# spi_adc.net
KiCad netlist of a schematic drawn in Altium Designer
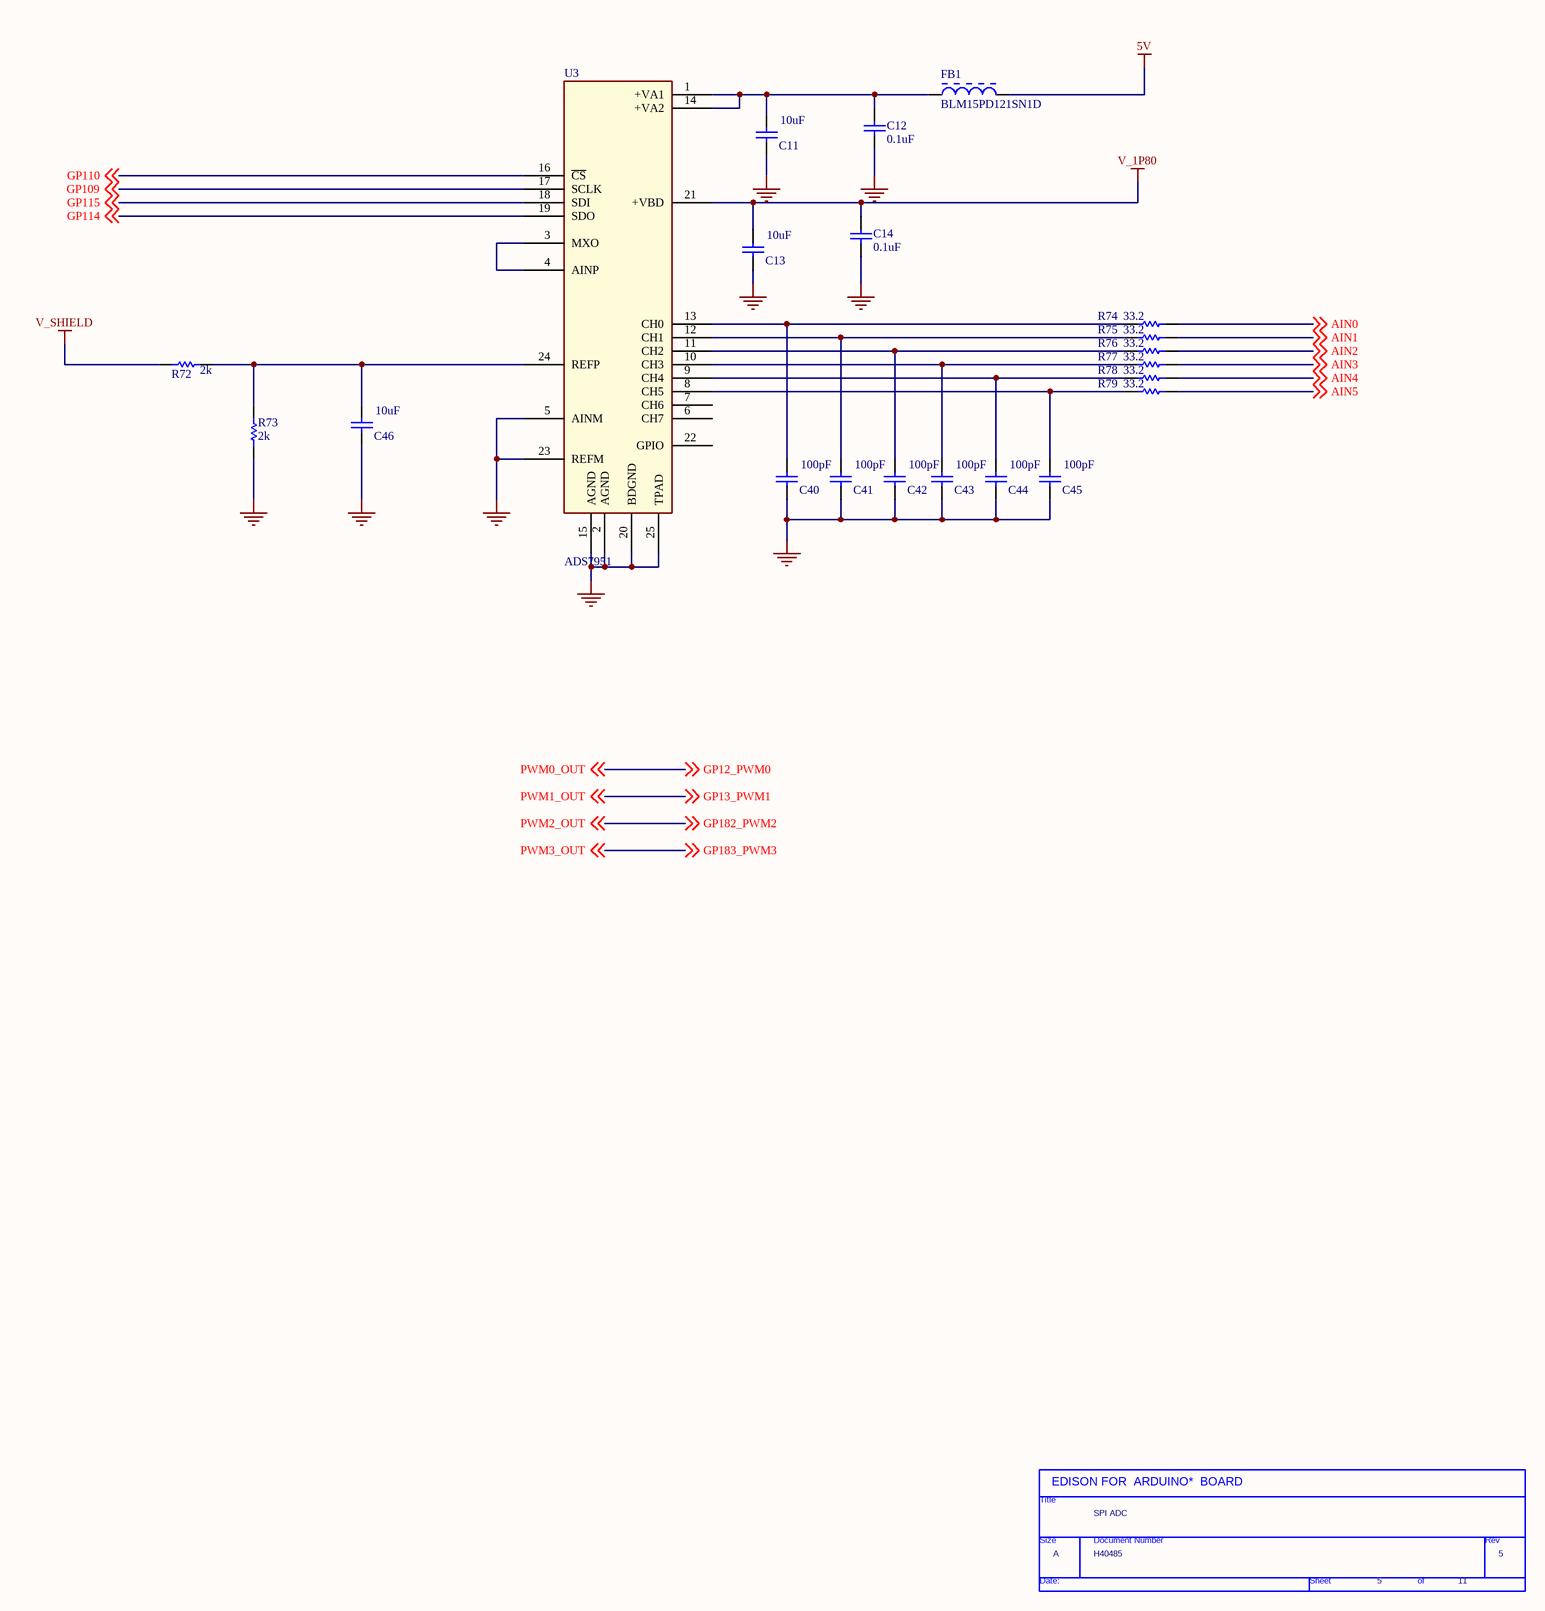
[diagram p0: spi_adc.SchDoc]

(export (version "E")
  (design (tool "Eeschema 10.0.6"))
  (components
    (comp (ref "*")
      (value "TitleBlock0")
      (fields
        (field (name "PAGE COUNT") "11")
        (field (name "PAGE NUMBER") "5")
        (field (name "PAGE SIZE") "A")
        (field (name "TITLE") "SPI ADC")
        (field (name "REVCODE") "5")
        (field (name "DOC") "H40485")
      )
      (libsource (lib "*") (part "TitleBlock0"))
    )
    (comp (ref "C11")
      (value "10uF")
      (footprint "CAPC0402(1005)60_L")
      (description "CAP 10uF 6.3V ±20% 0402 (1005 Metric) Thickness 0.6mm SMD")
      (fields (field (name "TOLERANCE") "±20%") (field (name "Comment") "CAP 10uF 6.3V 0402(1005)"))
      (libsource (lib "Altium Content Vault") (part "CMP-1034-02138-1"))
    )
    (comp (ref "C12")
      (value "0.1uF")
      (footprint "CAPC0201(0603)33_L")
      (description "CAP 1.5nF 10V ±20% 0201 (0603 Metric) Thickness 0.33mm SMD")
      (fields (field (name "TOLERANCE") "±20%") (field (name "Comment") "CAP 1.5nF 10V 0201(0603)"))
      (libsource (lib "Altium Content Vault") (part "CMP-1033-00601-1"))
    )
    (comp (ref "C13")
      (value "10uF")
      (footprint "CAPC0402(1005)60_L")
      (description "CAP 10uF 6.3V ±20% 0402 (1005 Metric) Thickness 0.6mm SMD")
      (fields (field (name "TOLERANCE") "±20%") (field (name "Comment") "CAP 10uF 6.3V 0402(1005)"))
      (libsource (lib "Altium Content Vault") (part "CMP-1034-02138-1"))
    )
    (comp (ref "C14")
      (value "0.1uF")
      (footprint "CAPC0201(0603)33_L")
      (description "CAP 1.5nF 10V ±20% 0201 (0603 Metric) Thickness 0.33mm SMD")
      (fields (field (name "TOLERANCE") "±20%") (field (name "Comment") "CAP 1.5nF 10V 0201(0603)"))
      (libsource (lib "Altium Content Vault") (part "CMP-1033-00601-1"))
    )
    (comp (ref "C40")
      (value "100pF")
      (footprint "CAPC0201(0603)33_M")
      (description "CAP 100pF 25V ±5% 0201 (0603 Metric) Thickness 0.33mm SMD")
      (fields (field (name "TOLERANCE") "±5%") (field (name "Comment") "CAP 100pF 25V 0201(0603)"))
      (libsource (lib "Altium Content Vault") (part "CMP-1033-00493-1"))
    )
    (comp (ref "C41")
      (value "100pF")
      (footprint "CAPC0201(0603)33_M")
      (description "CAP 100pF 25V ±5% 0201 (0603 Metric) Thickness 0.33mm SMD")
      (fields (field (name "TOLERANCE") "±5%") (field (name "Comment") "CAP 100pF 25V 0201(0603)"))
      (libsource (lib "Altium Content Vault") (part "CMP-1033-00493-1"))
    )
    (comp (ref "C42")
      (value "100pF")
      (footprint "CAPC0201(0603)33_M")
      (description "CAP 100pF 25V ±5% 0201 (0603 Metric) Thickness 0.33mm SMD")
      (fields (field (name "TOLERANCE") "±5%") (field (name "Comment") "CAP 100pF 25V 0201(0603)"))
      (libsource (lib "Altium Content Vault") (part "CMP-1033-00493-1"))
    )
    (comp (ref "C43")
      (value "100pF")
      (footprint "CAPC0201(0603)33_M")
      (description "CAP 100pF 25V ±5% 0201 (0603 Metric) Thickness 0.33mm SMD")
      (fields (field (name "TOLERANCE") "±5%") (field (name "Comment") "CAP 100pF 25V 0201(0603)"))
      (libsource (lib "Altium Content Vault") (part "CMP-1033-00493-1"))
    )
    (comp (ref "C44")
      (value "100pF")
      (footprint "CAPC0201(0603)33_M")
      (description "CAP 100pF 25V ±5% 0201 (0603 Metric) Thickness 0.33mm SMD")
      (fields (field (name "TOLERANCE") "±5%") (field (name "Comment") "CAP 100pF 25V 0201(0603)"))
      (libsource (lib "Altium Content Vault") (part "CMP-1033-00493-1"))
    )
    (comp (ref "C45")
      (value "100pF")
      (footprint "CAPC0201(0603)33_M")
      (description "CAP 100pF 25V ±5% 0201 (0603 Metric) Thickness 0.33mm SMD")
      (fields (field (name "TOLERANCE") "±5%") (field (name "Comment") "CAP 100pF 25V 0201(0603)"))
      (libsource (lib "Altium Content Vault") (part "CMP-1033-00493-1"))
    )
    (comp (ref "C46")
      (value "10uF")
      (footprint "CAPC0402(1005)60_L")
      (description "CAP 10uF 6.3V ±20% 0402 (1005 Metric) Thickness 0.6mm SMD")
      (fields (field (name "TOLERANCE") "±20%") (field (name "Comment") "CAP 10uF 6.3V 0402(1005)"))
      (libsource (lib "Altium Content Vault") (part "CMP-1034-02138-1"))
    )
    (comp (ref "FB1")
      (value "BLM15PD121SN1D")
      (footprint "MURA-BLM15-CHIP-2_V")
      (fields (field (name "MANUFACTURER") "Murata"))
      (libsource (lib "Altium Content Vault") (part "CMP-0686-00281-1"))
    )
    (comp (ref "R72")
      (value "2k")
      (footprint "RESC0201(0603)_N")
      (description "2K 0.05W 5% 0201 (0603 Metric)  SMD")
      (fields (field (name "TOLERANCE") "1 %") (field (name "POWER") "0.05 W"))
      (libsource (lib "Altium Content Vault") (part "CMP-1010-00081-1"))
    )
    (comp (ref "R73")
      (value "2k")
      (footprint "RESC0201(0603)_N")
      (description "2K 0.05W 5% 0201 (0603 Metric)  SMD")
      (fields (field (name "TOLERANCE") "1 %") (field (name "POWER") "0.05 W"))
      (libsource (lib "Altium Content Vault") (part "CMP-1010-00081-1"))
    )
    (comp (ref "R74")
      (value "33.2")
      (footprint "RESC0201(0603)_L")
      (description "33R2 0.05W 1% 0201 (0603 Metric)  SMD")
      (fields (field (name "POWER") "0.05 W") (field (name "TOLERANCE") "1 %"))
      (libsource (lib "Altium Content Vault") (part "CMP-1010-00248-1"))
    )
    (comp (ref "R75")
      (value "33.2")
      (footprint "RESC0201(0603)_L")
      (description "33R2 0.05W 1% 0201 (0603 Metric)  SMD")
      (fields (field (name "POWER") "0.05 W") (field (name "TOLERANCE") "1 %"))
      (libsource (lib "Altium Content Vault") (part "CMP-1010-00248-1"))
    )
    (comp (ref "R76")
      (value "33.2")
      (footprint "RESC0201(0603)_L")
      (description "33R2 0.05W 1% 0201 (0603 Metric)  SMD")
      (fields (field (name "POWER") "0.05 W") (field (name "TOLERANCE") "1 %"))
      (libsource (lib "Altium Content Vault") (part "CMP-1010-00248-1"))
    )
    (comp (ref "R77")
      (value "33.2")
      (footprint "RESC0201(0603)_L")
      (description "33R2 0.05W 1% 0201 (0603 Metric)  SMD")
      (fields (field (name "POWER") "0.05 W") (field (name "TOLERANCE") "1 %"))
      (libsource (lib "Altium Content Vault") (part "CMP-1010-00248-1"))
    )
    (comp (ref "R78")
      (value "33.2")
      (footprint "RESC0201(0603)_L")
      (description "33R2 0.05W 1% 0201 (0603 Metric)  SMD")
      (fields (field (name "POWER") "0.05 W") (field (name "TOLERANCE") "1 %"))
      (libsource (lib "Altium Content Vault") (part "CMP-1010-00248-1"))
    )
    (comp (ref "R79")
      (value "33.2")
      (footprint "RESC0201(0603)_L")
      (description "33R2 0.05W 1% 0201 (0603 Metric)  SMD")
      (fields (field (name "POWER") "0.05 W") (field (name "TOLERANCE") "1 %"))
      (libsource (lib "Altium Content Vault") (part "CMP-1010-00248-1"))
    )
    (comp (ref "U3")
      (value "ADS7951")
      (footprint "S-PVQFN-N24")
      (libsource (lib "elevate_lib") (part "ADS7951"))
    )
  )
  (nets
    (net (code "1") (name "5V") (class "Default")
      (node (ref "FB1") (pin "2") (pinfunction "2_2") (pintype "passive"))
    )
    (net (code "2") (name "AIN0") (class "Default")
      (node (ref "R74") (pin "2") (pinfunction "2_2") (pintype "passive"))
    )
    (net (code "3") (name "AIN1") (class "Default")
      (node (ref "R75") (pin "2") (pinfunction "2_2") (pintype "passive"))
    )
    (net (code "4") (name "AIN2") (class "Default")
      (node (ref "R76") (pin "2") (pinfunction "2_2") (pintype "passive"))
    )
    (net (code "5") (name "AIN3") (class "Default")
      (node (ref "R77") (pin "2") (pinfunction "2_2") (pintype "passive"))
    )
    (net (code "6") (name "AIN4") (class "Default")
      (node (ref "R78") (pin "2") (pinfunction "2_2") (pintype "passive"))
    )
    (net (code "7") (name "AIN5") (class "Default")
      (node (ref "R79") (pin "2") (pinfunction "2_2") (pintype "passive"))
    )
    (net (code "8") (name "GND") (class "Default")
      (node (ref "C11") (pin "1") (pinfunction "1_1") (pintype "passive"))
      (node (ref "C12") (pin "2") (pinfunction "2_2") (pintype "passive"))
      (node (ref "C13") (pin "1") (pinfunction "1_1") (pintype "passive"))
      (node (ref "C14") (pin "2") (pinfunction "2_2") (pintype "passive"))
      (node (ref "C40") (pin "2") (pinfunction "2_2") (pintype "passive"))
      (node (ref "C41") (pin "2") (pinfunction "2_2") (pintype "passive"))
      (node (ref "C42") (pin "2") (pinfunction "2_2") (pintype "passive"))
      (node (ref "C43") (pin "2") (pinfunction "2_2") (pintype "passive"))
      (node (ref "C44") (pin "2") (pinfunction "2_2") (pintype "passive"))
      (node (ref "C45") (pin "2") (pinfunction "2_2") (pintype "passive"))
      (node (ref "C46") (pin "1") (pinfunction "1_1") (pintype "passive"))
      (node (ref "R73") (pin "1") (pinfunction "1_1") (pintype "passive"))
      (node (ref "U3") (pin "15") (pinfunction "AGND_15") (pintype "power_in"))
      (node (ref "U3") (pin "2") (pinfunction "AGND_2") (pintype "power_in"))
      (node (ref "U3") (pin "20") (pinfunction "BDGND_20") (pintype "power_in"))
      (node (ref "U3") (pin "23") (pinfunction "REFM_23") (pintype "passive"))
      (node (ref "U3") (pin "25") (pinfunction "TPAD_25") (pintype "passive"))
      (node (ref "U3") (pin "5") (pinfunction "AINM_5") (pintype "passive"))
    )
    (net (code "11") (name "GP109") (class "Default")
      (node (ref "U3") (pin "17") (pinfunction "SCLK_17") (pintype "passive"))
    )
    (net (code "12") (name "GP110") (class "Default")
      (node (ref "U3") (pin "16") (pinfunction "~{CS}_16") (pintype "passive"))
    )
    (net (code "13") (name "GP114") (class "Default")
      (node (ref "U3") (pin "19") (pinfunction "SDO_19") (pintype "passive"))
    )
    (net (code "14") (name "GP115") (class "Default")
      (node (ref "U3") (pin "18") (pinfunction "SDI_18") (pintype "passive"))
    )
    (net (code "17") (name "Net-(U3-+VA1)") (class "Default")
      (node (ref "C11") (pin "2") (pinfunction "2_2") (pintype "passive"))
      (node (ref "C12") (pin "1") (pinfunction "1_1") (pintype "passive"))
      (node (ref "FB1") (pin "1") (pinfunction "1_1") (pintype "passive"))
      (node (ref "U3") (pin "1") (pinfunction "+VA1_1") (pintype "passive"))
      (node (ref "U3") (pin "14") (pinfunction "+VA2_14") (pintype "passive"))
    )
    (net (code "18") (name "Net-(U3-AINP)") (class "Default")
      (node (ref "U3") (pin "3") (pinfunction "MXO_3") (pintype "passive"))
      (node (ref "U3") (pin "4") (pinfunction "AINP_4") (pintype "passive"))
    )
    (net (code "19") (name "Net-(U3-CH0)") (class "Default")
      (node (ref "C40") (pin "1") (pinfunction "1_1") (pintype "passive"))
      (node (ref "R74") (pin "1") (pinfunction "1_1") (pintype "passive"))
      (node (ref "U3") (pin "13") (pinfunction "CH0_13") (pintype "passive"))
    )
    (net (code "20") (name "Net-(U3-CH1)") (class "Default")
      (node (ref "C41") (pin "1") (pinfunction "1_1") (pintype "passive"))
      (node (ref "R75") (pin "1") (pinfunction "1_1") (pintype "passive"))
      (node (ref "U3") (pin "12") (pinfunction "CH1_12") (pintype "passive"))
    )
    (net (code "21") (name "Net-(U3-CH2)") (class "Default")
      (node (ref "C42") (pin "1") (pinfunction "1_1") (pintype "passive"))
      (node (ref "R76") (pin "1") (pinfunction "1_1") (pintype "passive"))
      (node (ref "U3") (pin "11") (pinfunction "CH2_11") (pintype "passive"))
    )
    (net (code "22") (name "Net-(U3-CH3)") (class "Default")
      (node (ref "C43") (pin "1") (pinfunction "1_1") (pintype "passive"))
      (node (ref "R77") (pin "1") (pinfunction "1_1") (pintype "passive"))
      (node (ref "U3") (pin "10") (pinfunction "CH3_10") (pintype "passive"))
    )
    (net (code "23") (name "Net-(U3-CH4)") (class "Default")
      (node (ref "C44") (pin "1") (pinfunction "1_1") (pintype "passive"))
      (node (ref "R78") (pin "1") (pinfunction "1_1") (pintype "passive"))
      (node (ref "U3") (pin "9") (pinfunction "CH4_9") (pintype "passive"))
    )
    (net (code "24") (name "Net-(U3-CH5)") (class "Default")
      (node (ref "C45") (pin "1") (pinfunction "1_1") (pintype "passive"))
      (node (ref "R79") (pin "1") (pinfunction "1_1") (pintype "passive"))
      (node (ref "U3") (pin "8") (pinfunction "CH5_8") (pintype "passive"))
    )
    (net (code "25") (name "Net-(U3-REFP)") (class "Default")
      (node (ref "C46") (pin "2") (pinfunction "2_2") (pintype "passive"))
      (node (ref "R72") (pin "2") (pinfunction "2_2") (pintype "passive"))
      (node (ref "R73") (pin "2") (pinfunction "2_2") (pintype "passive"))
      (node (ref "U3") (pin "24") (pinfunction "REFP_24") (pintype "passive"))
    )
    (net (code "26") (name "V_1P80") (class "Default")
      (node (ref "C13") (pin "2") (pinfunction "2_2") (pintype "passive"))
      (node (ref "C14") (pin "1") (pinfunction "1_1") (pintype "passive"))
      (node (ref "U3") (pin "21") (pinfunction "+VBD_21") (pintype "passive"))
    )
    (net (code "27") (name "V_SHIELD") (class "Default")
      (node (ref "R72") (pin "1") (pinfunction "1_1") (pintype "passive"))
    )
    (net (code "28") (name "unconnected-(U3-CH6-Pad7)") (class "Default")
      (node (ref "U3") (pin "7") (pinfunction "CH6_7") (pintype "passive"))
    )
    (net (code "29") (name "unconnected-(U3-CH7-Pad6)") (class "Default")
      (node (ref "U3") (pin "6") (pinfunction "CH7_6") (pintype "passive"))
    )
    (net (code "30") (name "unconnected-(U3-GPIO-Pad22)") (class "Default")
      (node (ref "U3") (pin "22") (pinfunction "GPIO_22") (pintype "passive"))
    )
  )
)
